# 741_Operational_Amplifier.net
KiCad netlist of a schematic drawn in Altium Designer
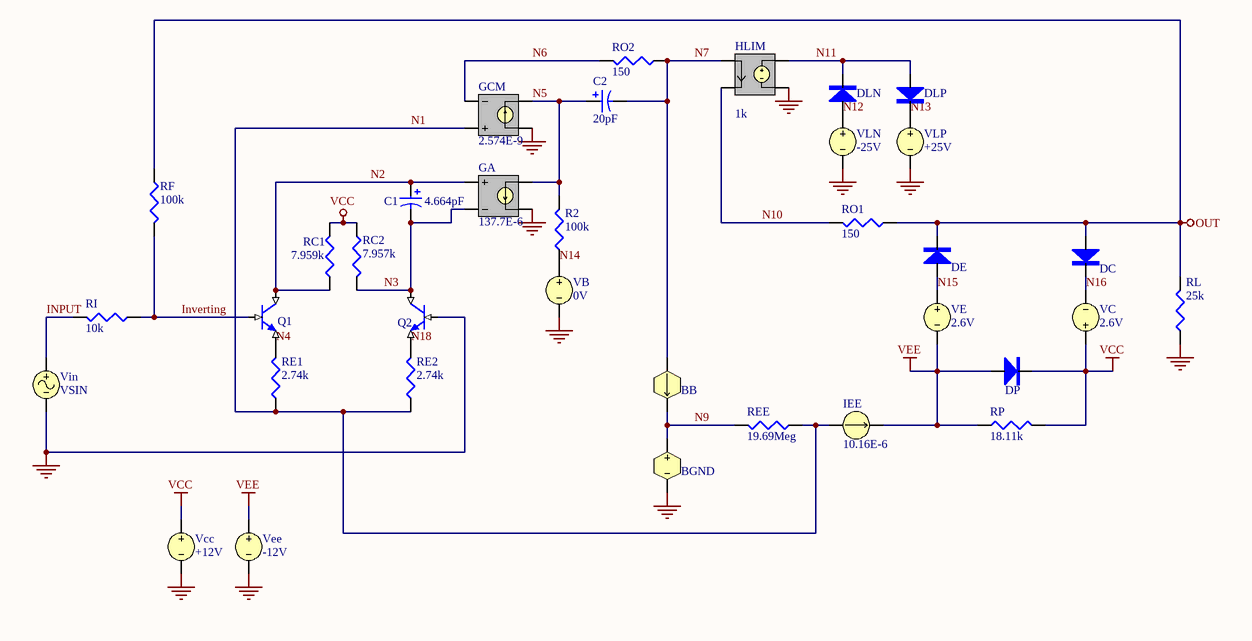
[diagram p0: 741 Operational Amplifier.schdoc]

(export (version "E")
  (design (tool "Eeschema 10.0.6"))
  (components
    (comp (ref "BB")
      (value "I(VB)*10.61E6-I(VC)*10E6+I(VE)*10E6+I(VLP)*10E6-I(VLN)*10E6")
      (description "Non-Linear Dependent Current Source")
      (libsource (lib "*") (part "BISRC"))
    )
    (comp (ref "BGND")
      (value "V(VCC)*.5+V(VEE)*.5")
      (description "Non-Linear Dependent Voltage Source")
      (libsource (lib "*") (part "BVSRC"))
    )
    (comp (ref "C1") (value "4.664pF") (description "Bi-Polar Capacitor") (libsource (lib "*") (part "CAP2")))
    (comp (ref "C2") (value "20pF") (description "Bi-Polar Capacitor") (libsource (lib "*") (part "CAP2")))
    (comp (ref "DC") (value "1N914") (description "Diode") (libsource (lib "") (part "1N914_2")))
    (comp (ref "DE") (value "1N914") (description "Diode") (libsource (lib "*") (part "1N914")))
    (comp (ref "DLN") (value "1N914") (description "Diode") (libsource (lib "*") (part "1N914")))
    (comp (ref "DLP") (value "1N914") (description "Diode") (libsource (lib "") (part "1N914_2")))
    (comp (ref "DP") (value "1N914") (description "Diode") (libsource (lib "") (part "1N914_1")))
    (comp (ref "GA")
      (value "137.7E-6")
      (description "Voltage Controlled Current Source")
      (fields (field (name "GAIN") "137.7E-6"))
      (libsource (lib "") (part "GSRC_1"))
    )
    (comp (ref "GCM")
      (value "2.574E-9")
      (description "Voltage Controlled Current Source")
      (fields (field (name "GAIN") "2.574E-9"))
      (libsource (lib "*") (part "GSRC"))
    )
    (comp (ref "HLIM")
      (value "1k")
      (description "Current Controlled Voltage Source")
      (fields (field (name "GAIN") "1k"))
      (libsource (lib "*") (part "HSRC"))
    )
    (comp (ref "IEE") (value "10.16E-6") (description "Current Source") (libsource (lib "*") (part "ISRC")))
    (comp (ref "Q1") (value "2N2222A") (description "NPN BJT") (libsource (lib "*") (part "2N2222A")))
    (comp (ref "Q2") (value "2N2222A") (description "NPN BJT") (libsource (lib "*") (part "2N2222A")))
    (comp (ref "R2") (value "100k") (description "Resistor") (libsource (lib "") (part "RES_2")))
    (comp (ref "RC1") (value "7.959k") (description "Resistor") (libsource (lib "") (part "RES_2")))
    (comp (ref "RC2") (value "7.957k") (description "Resistor") (libsource (lib "") (part "RES_1")))
    (comp (ref "RE1") (value "2.74k") (description "Resistor") (libsource (lib "") (part "RES_2")))
    (comp (ref "RE2") (value "2.74k") (description "Resistor") (libsource (lib "") (part "RES_2")))
    (comp (ref "REE") (value "19.69Meg") (description "Resistor") (libsource (lib "*") (part "RES")))
    (comp (ref "RF") (value "100k") (description "Resistor") (libsource (lib "") (part "RES_1")))
    (comp (ref "RI") (value "10k") (description "Resistor") (libsource (lib "*") (part "RES")))
    (comp (ref "RL") (value "25k") (description "Resistor") (libsource (lib "") (part "RES_2")))
    (comp (ref "RO1") (value "150") (description "Resistor") (libsource (lib "*") (part "RES")))
    (comp (ref "RO2") (value "150") (description "Resistor") (libsource (lib "*") (part "RES")))
    (comp (ref "RP") (value "18.11k") (description "Resistor") (libsource (lib "") (part "RES_3")))
    (comp (ref "VB") (value "0V") (description "Voltage Source") (libsource (lib "*") (part "VSRC")))
    (comp (ref "VC") (value "2.6V") (description "Voltage Source") (libsource (lib "*") (part "VSRC")))
    (comp (ref "Vcc") (value "+12V") (description "Voltage Source") (libsource (lib "*") (part "VSRC")))
    (comp (ref "VE") (value "2.6V") (description "Voltage Source") (libsource (lib "*") (part "VSRC")))
    (comp (ref "Vee") (value "-12V") (description "Voltage Source") (libsource (lib "*") (part "VSRC")))
    (comp (ref "Vin")
      (value "VSIN")
      (description "Sinusoidal Voltage Source")
      (libsource (lib "*") (part "VSIN"))
    )
    (comp (ref "VLN") (value "-25V") (description "Voltage Source") (libsource (lib "*") (part "VSRC")))
    (comp (ref "VLP") (value "+25V") (description "Voltage Source") (libsource (lib "*") (part "VSRC")))
  )
  (nets
    (net (code "1") (name "/INPUT") (class "Default")
      (node (ref "RI") (pin "1") (pinfunction "TOP_1") (pintype "passive"))
      (node (ref "Vin") (pin "1") (pinfunction "1_1") (pintype "passive"))
    )
    (net (code "2") (name "/Inverting") (class "Default")
      (node (ref "Q1") (pin "2") (pinfunction "B_2") (pintype "input"))
      (node (ref "RF") (pin "1") (pinfunction "TOP_1") (pintype "passive"))
      (node (ref "RI") (pin "2") (pinfunction "BOT_2") (pintype "passive"))
    )
    (net (code "3") (name "/N1") (class "Default")
      (node (ref "GCM") (pin "1") (pinfunction "NC+_1") (pintype "passive"))
      (node (ref "IEE") (pin "1") (pinfunction "1_1") (pintype "passive"))
      (node (ref "RE1") (pin "2") (pinfunction "BOT_2") (pintype "passive"))
      (node (ref "RE2") (pin "2") (pinfunction "BOT_2") (pintype "passive"))
      (node (ref "REE") (pin "2") (pinfunction "BOT_2") (pintype "passive"))
    )
    (net (code "4") (name "/N2") (class "Default")
      (node (ref "C1") (pin "1") (pinfunction "1_1") (pintype "passive"))
      (node (ref "GA") (pin "1") (pinfunction "NC+_1") (pintype "passive"))
      (node (ref "Q1") (pin "1") (pinfunction "C_1") (pintype "input"))
      (node (ref "RC1") (pin "2") (pinfunction "BOT_2") (pintype "passive"))
    )
    (net (code "5") (name "/N3") (class "Default")
      (node (ref "C1") (pin "2") (pinfunction "2_2") (pintype "passive"))
      (node (ref "GA") (pin "2") (pinfunction "NC-_2") (pintype "passive"))
      (node (ref "Q2") (pin "1") (pinfunction "C_1") (pintype "input"))
      (node (ref "RC2") (pin "1") (pinfunction "TOP_1") (pintype "passive"))
    )
    (net (code "6") (name "/N4") (class "Default")
      (node (ref "Q1") (pin "3") (pinfunction "E_3") (pintype "input"))
      (node (ref "RE1") (pin "1") (pinfunction "TOP_1") (pintype "passive"))
    )
    (net (code "7") (name "/N5") (class "Default")
      (node (ref "C2") (pin "1") (pinfunction "1_1") (pintype "passive"))
      (node (ref "GA") (pin "3") (pinfunction "N+_3") (pintype "passive"))
      (node (ref "GCM") (pin "4") (pinfunction "N-_4") (pintype "passive"))
      (node (ref "R2") (pin "1") (pinfunction "TOP_1") (pintype "passive"))
    )
    (net (code "8") (name "/N6") (class "Default")
      (node (ref "GCM") (pin "2") (pinfunction "NC-_2") (pintype "passive"))
      (node (ref "RO2") (pin "1") (pinfunction "TOP_1") (pintype "passive"))
    )
    (net (code "9") (name "/N7") (class "Default")
      (node (ref "BB") (pin "1") (pinfunction "1_1") (pintype "passive"))
      (node (ref "C2") (pin "2") (pinfunction "2_2") (pintype "passive"))
      (node (ref "HLIM") (pin "1") (pinfunction "NC+_1") (pintype "passive"))
      (node (ref "RO2") (pin "2") (pinfunction "BOT_2") (pintype "passive"))
    )
    (net (code "10") (name "/N9") (class "Default")
      (node (ref "BB") (pin "2") (pinfunction "2_2") (pintype "passive"))
      (node (ref "BGND") (pin "1") (pinfunction "1_1") (pintype "passive"))
      (node (ref "REE") (pin "1") (pinfunction "TOP_1") (pintype "passive"))
    )
    (net (code "11") (name "/N10") (class "Default")
      (node (ref "HLIM") (pin "2") (pinfunction "NC-_2") (pintype "passive"))
      (node (ref "RO1") (pin "1") (pinfunction "TOP_1") (pintype "passive"))
    )
    (net (code "12") (name "/N11") (class "Default")
      (node (ref "DLN") (pin "2") (pinfunction "K_2") (pintype "passive"))
      (node (ref "DLP") (pin "1") (pinfunction "A_1") (pintype "passive"))
      (node (ref "HLIM") (pin "3") (pinfunction "N+_3") (pintype "passive"))
    )
    (net (code "13") (name "/N12") (class "Default")
      (node (ref "DLN") (pin "1") (pinfunction "A_1") (pintype "passive"))
      (node (ref "VLN") (pin "1") (pinfunction "1_1") (pintype "passive"))
    )
    (net (code "14") (name "/N13") (class "Default")
      (node (ref "DLP") (pin "2") (pinfunction "K_2") (pintype "passive"))
      (node (ref "VLP") (pin "1") (pinfunction "1_1") (pintype "passive"))
    )
    (net (code "15") (name "/N14") (class "Default")
      (node (ref "R2") (pin "2") (pinfunction "BOT_2") (pintype "passive"))
      (node (ref "VB") (pin "1") (pinfunction "1_1") (pintype "passive"))
    )
    (net (code "16") (name "/N15") (class "Default")
      (node (ref "DE") (pin "1") (pinfunction "A_1") (pintype "passive"))
      (node (ref "VE") (pin "1") (pinfunction "1_1") (pintype "passive"))
    )
    (net (code "17") (name "/N16") (class "Default")
      (node (ref "DC") (pin "2") (pinfunction "K_2") (pintype "passive"))
      (node (ref "VC") (pin "2") (pinfunction "2_2") (pintype "passive"))
    )
    (net (code "18") (name "/N18") (class "Default")
      (node (ref "Q2") (pin "3") (pinfunction "E_3") (pintype "input"))
      (node (ref "RE2") (pin "1") (pinfunction "TOP_1") (pintype "passive"))
    )
    (net (code "19") (name "GND") (class "Default")
      (node (ref "BGND") (pin "2") (pinfunction "2_2") (pintype "passive"))
      (node (ref "GA") (pin "4") (pinfunction "N-_4") (pintype "passive"))
      (node (ref "GCM") (pin "3") (pinfunction "N+_3") (pintype "passive"))
      (node (ref "HLIM") (pin "4") (pinfunction "N-_4") (pintype "passive"))
      (node (ref "Q2") (pin "2") (pinfunction "B_2") (pintype "input"))
      (node (ref "RL") (pin "2") (pinfunction "BOT_2") (pintype "passive"))
      (node (ref "VB") (pin "2") (pinfunction "2_2") (pintype "passive"))
      (node (ref "VLN") (pin "2") (pinfunction "2_2") (pintype "passive"))
      (node (ref "VLP") (pin "2") (pinfunction "2_2") (pintype "passive"))
      (node (ref "Vcc") (pin "2") (pinfunction "2_2") (pintype "passive"))
      (node (ref "Vee") (pin "2") (pinfunction "2_2") (pintype "passive"))
      (node (ref "Vin") (pin "2") (pinfunction "2_2") (pintype "passive"))
    )
    (net (code "20") (name "OUT") (class "Default")
      (node (ref "DC") (pin "1") (pinfunction "A_1") (pintype "passive"))
      (node (ref "DE") (pin "2") (pinfunction "K_2") (pintype "passive"))
      (node (ref "RF") (pin "2") (pinfunction "BOT_2") (pintype "passive"))
      (node (ref "RL") (pin "1") (pinfunction "TOP_1") (pintype "passive"))
      (node (ref "RO1") (pin "2") (pinfunction "BOT_2") (pintype "passive"))
    )
    (net (code "21") (name "VCC") (class "Default")
      (node (ref "DP") (pin "2") (pinfunction "K_2") (pintype "passive"))
      (node (ref "RC1") (pin "1") (pinfunction "TOP_1") (pintype "passive"))
      (node (ref "RC2") (pin "2") (pinfunction "BOT_2") (pintype "passive"))
      (node (ref "RP") (pin "1") (pinfunction "TOP_1") (pintype "passive"))
      (node (ref "VC") (pin "1") (pinfunction "1_1") (pintype "passive"))
      (node (ref "Vcc") (pin "1") (pinfunction "1_1") (pintype "passive"))
    )
    (net (code "22") (name "VEE") (class "Default")
      (node (ref "DP") (pin "1") (pinfunction "A_1") (pintype "passive"))
      (node (ref "IEE") (pin "2") (pinfunction "2_2") (pintype "passive"))
      (node (ref "RP") (pin "2") (pinfunction "BOT_2") (pintype "passive"))
      (node (ref "VE") (pin "2") (pinfunction "2_2") (pintype "passive"))
      (node (ref "Vee") (pin "1") (pinfunction "1_1") (pintype "passive"))
    )
  )
)
